# sht25_v_1_0.net
KiCad netlist of a schematic drawn in EAGLE
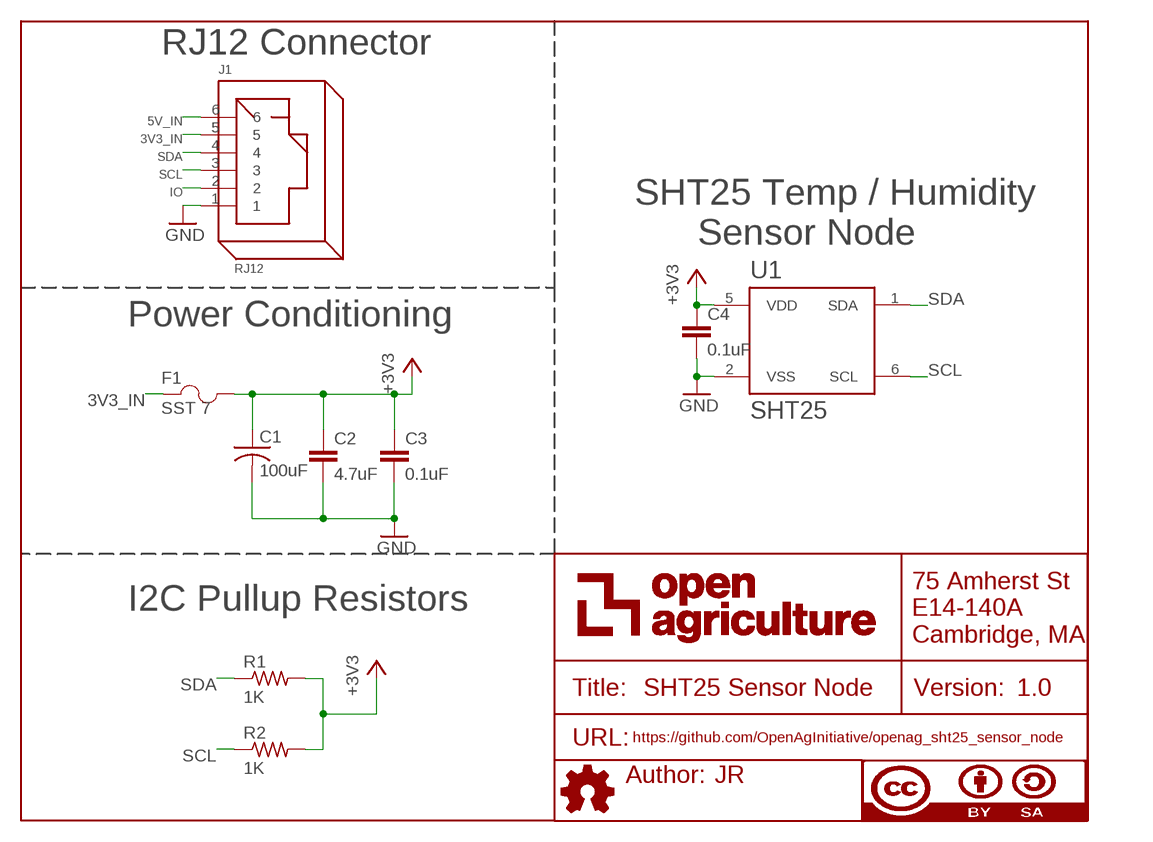
[diagram p0: schematic, sheet 1]

(export (version "E")
  (design (tool "Eeschema 10.0.6"))
  (components
    (comp (ref "C1")
      (value "100uF")
      (footprint "eagle-import:EEE-1HA101UP")
      (libsource (lib "eagle-import") (part "100UF-EEE-1HA101UP"))
    )
    (comp (ref "C2")
      (value "4.7uF")
      (footprint "eagle-import:C0805")
      (libsource (lib "eagle-import") (part "4.7UF-CL21A475KBQNNNE"))
    )
    (comp (ref "C3")
      (value "0.1uF")
      (footprint "eagle-import:C0603")
      (libsource (lib "eagle-import") (part "0.1UF-C0603C104K5RACTU"))
    )
    (comp (ref "C4")
      (value "0.1uF")
      (footprint "eagle-import:C0603")
      (libsource (lib "eagle-import") (part "0.1UF-C0603C104K5RACTU"))
    )
    (comp (ref "F1")
      (value "SST 7")
      (footprint "eagle-import:SS")
      (libsource (lib "eagle-import") (part "SST_7"))
    )
    (comp (ref "FRAME1")
      (value "DOCFIELD")
      (footprint "eagle-import:DOCFIELD")
      (fields
        (field (name "AUTHOR") "JR")
        (field (name "TITLE") "SHT25 Sensor Node")
        (field (name "URL") "https://github.com/OpenAgInitiative/openag_sht25_sensor_node")
      )
      (libsource (lib "eagle-import") (part "DOCFIELD"))
    )
    (comp (ref "J1")
      (value "RJ12")
      (footprint "eagle-import:RJ12")
      (libsource (lib "eagle-import") (part "A-2004-1-4-LP-N-R"))
    )
    (comp (ref "R1")
      (value "1K")
      (footprint "eagle-import:RC0603N")
      (libsource (lib "eagle-import") (part "1K-ERJ-PB3D1001V"))
    )
    (comp (ref "R2")
      (value "1K")
      (footprint "eagle-import:RC0603N")
      (libsource (lib "eagle-import") (part "1K-ERJ-PB3D1001V"))
    )
    (comp (ref "U1")
      (value "SHT25")
      (footprint "eagle-import:SHT2X")
      (libsource (lib "eagle-import") (part "SHT25"))
    )
  )
  (nets
    (net (code "1") (name "+3V3") (class "Default")
      (node (ref "C1") (pin "+") (pinfunction "1(+)_+") (pintype "passive"))
      (node (ref "C2") (pin "1") (pinfunction "1_1") (pintype "passive"))
      (node (ref "C3") (pin "1") (pinfunction "1_1") (pintype "passive"))
      (node (ref "C4") (pin "1") (pinfunction "1_1") (pintype "passive"))
      (node (ref "F1") (pin "2") (pinfunction "2_2") (pintype "passive"))
      (node (ref "R1") (pin "2") (pinfunction "2_2") (pintype "passive"))
      (node (ref "R2") (pin "2") (pinfunction "2_2") (pintype "passive"))
      (node (ref "U1") (pin "5") (pinfunction "VDD_5") (pintype "power_in"))
    )
    (net (code "2") (name "3V3_IN") (class "Default")
      (node (ref "F1") (pin "1") (pinfunction "1_1") (pintype "passive"))
      (node (ref "J1") (pin "5") (pinfunction "5_5") (pintype "bidirectional"))
    )
    (net (code "3") (name "5V_IN") (class "Default")
      (node (ref "J1") (pin "6") (pinfunction "6_6") (pintype "bidirectional"))
    )
    (net (code "4") (name "GND") (class "Default")
      (node (ref "C1") (pin "-") (pinfunction "2(-)_-") (pintype "passive"))
      (node (ref "C2") (pin "2") (pinfunction "2_2") (pintype "passive"))
      (node (ref "C3") (pin "2") (pinfunction "2_2") (pintype "passive"))
      (node (ref "C4") (pin "2") (pinfunction "2_2") (pintype "passive"))
      (node (ref "J1") (pin "1") (pinfunction "1_1") (pintype "bidirectional"))
      (node (ref "U1") (pin "2") (pinfunction "VSS_2") (pintype "power_in"))
    )
    (net (code "5") (name "IO") (class "Default")
      (node (ref "J1") (pin "2") (pinfunction "2_2") (pintype "bidirectional"))
    )
    (net (code "6") (name "SCL") (class "Default")
      (node (ref "J1") (pin "3") (pinfunction "3_3") (pintype "bidirectional"))
      (node (ref "R2") (pin "1") (pinfunction "1_1") (pintype "passive"))
      (node (ref "U1") (pin "6") (pinfunction "SCL_6") (pintype "bidirectional"))
    )
    (net (code "7") (name "SDA") (class "Default")
      (node (ref "J1") (pin "4") (pinfunction "4_4") (pintype "bidirectional"))
      (node (ref "R1") (pin "1") (pinfunction "1_1") (pintype "passive"))
      (node (ref "U1") (pin "1") (pinfunction "SDA_1") (pintype "bidirectional"))
    )
  )
)
